# SCH_LatencyMeter_Loc2_2024-01-18.net
KiCad netlist of a schematic drawn in EasyEDA
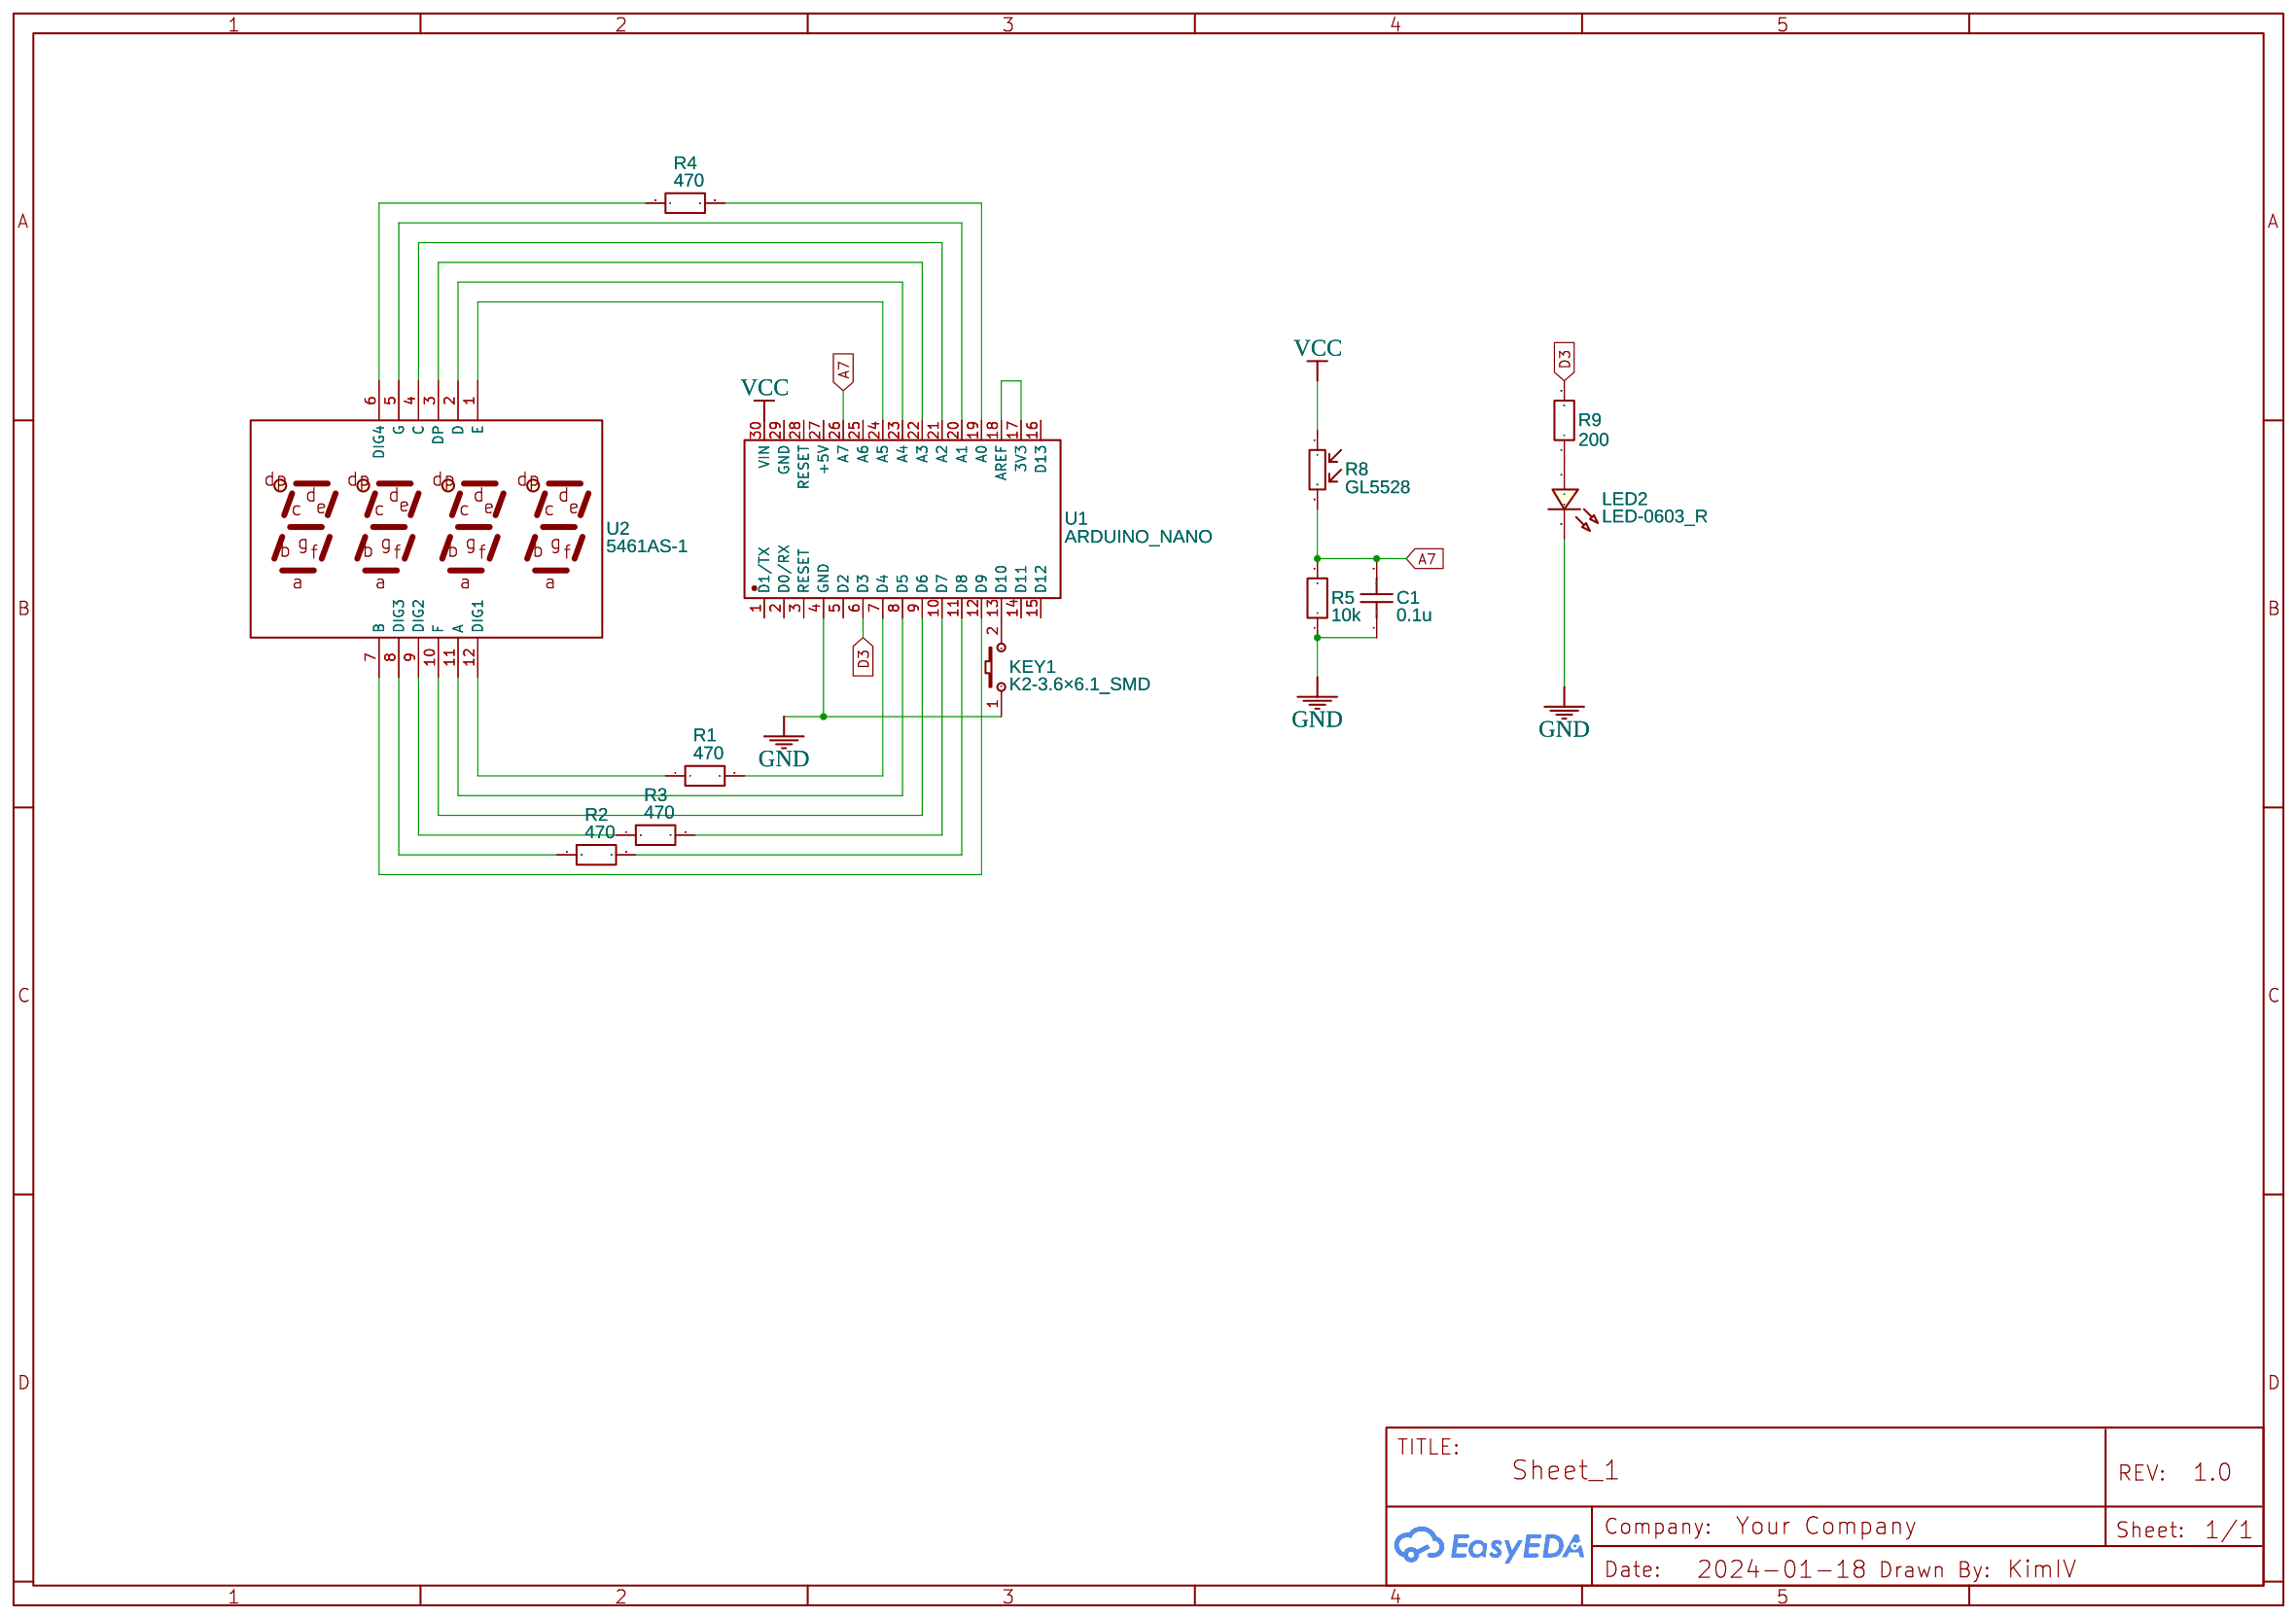
[diagram p0: schematic sheet]

(export (version "E")
  (design (tool "Eeschema 10.0.6"))
  (components
    (comp (ref "C1") (value "0.1u") (libsource (lib "") (part "C_0603_US")))
    (comp (ref "KEY1")
      (value "K2-3.6×6.1_SMD")
      (fields (field (name "Manufacturer Part") "K2-1107ST-A4SW-06"))
      (libsource (lib "") (part "K2-3.6×6.1_SMD"))
    )
    (comp (ref "LED2")
      (value "LED-0603_R")
      (fields
        (field (name "Manufacturer Part") "19-217/R6C-AL1M2VY/3T")
        (field (name "Manufacturer") "EVERLIGHT(台湾亿光)")
      )
      (libsource (lib "") (part "LED-0603_R"))
    )
    (comp (ref "R1") (value "470") (libsource (lib "") (part "R_0603_EU_1")))
    (comp (ref "R2") (value "470") (libsource (lib "") (part "R_0603_EU_1")))
    (comp (ref "R3") (value "470") (libsource (lib "") (part "R_0603_EU_1")))
    (comp (ref "R4") (value "470") (libsource (lib "") (part "R_0603_EU_1")))
    (comp (ref "R5") (value "10k") (libsource (lib "") (part "R_0603_EU")))
    (comp (ref "R8")
      (value "GL5528")
      (fields (field (name "Manufacturer") "森霸"))
      (libsource (lib "") (part "GL5528"))
    )
    (comp (ref "R9") (value "200") (libsource (lib "") (part "R_0603_EU")))
    (comp (ref "U1") (value "ARDUINO_NANO") (libsource (lib "") (part "ARDUINO_NANO")))
    (comp (ref "U2") (value "5461AS-1") (libsource (lib "") (part "5461AS-1")))
  )
  (nets
    (net (code "1") (name "A7") (class "Default")
      (node (ref "C1") (pin "2") (pinfunction "2_2") (pintype "unspecified"))
      (node (ref "R5") (pin "2") (pinfunction "2_2") (pintype "unspecified"))
      (node (ref "R8") (pin "2") (pinfunction "2_2") (pintype "input"))
      (node (ref "U1") (pin "26") (pinfunction "A7_26") (pintype "unspecified"))
    )
    (net (code "2") (name "D3") (class "Default")
      (node (ref "R9") (pin "2") (pinfunction "2_2") (pintype "unspecified"))
      (node (ref "U1") (pin "6") (pinfunction "D3_6") (pintype "unspecified"))
    )
    (net (code "3") (name "GND") (class "Default")
      (node (ref "C1") (pin "1") (pinfunction "1_1") (pintype "unspecified"))
      (node (ref "KEY1") (pin "1") (pinfunction "1_1") (pintype "unspecified"))
      (node (ref "LED2") (pin "2") (pinfunction "2_2") (pintype "unspecified"))
      (node (ref "R5") (pin "1") (pinfunction "1_1") (pintype "unspecified"))
      (node (ref "U1") (pin "4") (pinfunction "GND_4") (pintype "unspecified"))
    )
    (net (code "4") (name "Net-(LED2-Pad1)") (class "Default")
      (node (ref "LED2") (pin "1") (pinfunction "1_1") (pintype "unspecified"))
      (node (ref "R9") (pin "1") (pinfunction "1_1") (pintype "unspecified"))
    )
    (net (code "5") (name "Net-(U1-3V3)") (class "Default")
      (node (ref "U1") (pin "17") (pinfunction "3V3_17") (pintype "unspecified"))
      (node (ref "U1") (pin "18") (pinfunction "AREF_18") (pintype "unspecified"))
    )
    (net (code "6") (name "Net-(U1-A0)") (class "Default")
      (node (ref "R4") (pin "2") (pinfunction "2_2") (pintype "unspecified"))
      (node (ref "U1") (pin "19") (pinfunction "A0_19") (pintype "unspecified"))
    )
    (net (code "7") (name "Net-(U1-A1)") (class "Default")
      (node (ref "U1") (pin "20") (pinfunction "A1_20") (pintype "unspecified"))
      (node (ref "U2") (pin "5") (pinfunction "G_5") (pintype "input"))
    )
    (net (code "8") (name "Net-(U1-A2)") (class "Default")
      (node (ref "U1") (pin "21") (pinfunction "A2_21") (pintype "unspecified"))
      (node (ref "U2") (pin "4") (pinfunction "C_4") (pintype "input"))
    )
    (net (code "9") (name "Net-(U1-A3)") (class "Default")
      (node (ref "U1") (pin "22") (pinfunction "A3_22") (pintype "unspecified"))
      (node (ref "U2") (pin "3") (pinfunction "DP_3") (pintype "input"))
    )
    (net (code "10") (name "Net-(U1-A4)") (class "Default")
      (node (ref "U1") (pin "23") (pinfunction "A4_23") (pintype "unspecified"))
      (node (ref "U2") (pin "2") (pinfunction "D_2") (pintype "input"))
    )
    (net (code "11") (name "Net-(U1-A5)") (class "Default")
      (node (ref "U1") (pin "24") (pinfunction "A5_24") (pintype "unspecified"))
      (node (ref "U2") (pin "1") (pinfunction "E_1") (pintype "input"))
    )
    (net (code "12") (name "Net-(U1-D4)") (class "Default")
      (node (ref "R1") (pin "2") (pinfunction "2_2") (pintype "unspecified"))
      (node (ref "U1") (pin "7") (pinfunction "D4_7") (pintype "unspecified"))
    )
    (net (code "13") (name "Net-(U1-D5)") (class "Default")
      (node (ref "U1") (pin "8") (pinfunction "D5_8") (pintype "unspecified"))
      (node (ref "U2") (pin "11") (pinfunction "A_11") (pintype "input"))
    )
    (net (code "14") (name "Net-(U1-D6)") (class "Default")
      (node (ref "U1") (pin "9") (pinfunction "D6_9") (pintype "unspecified"))
      (node (ref "U2") (pin "10") (pinfunction "F_10") (pintype "input"))
    )
    (net (code "15") (name "Net-(U1-D7)") (class "Default")
      (node (ref "R3") (pin "2") (pinfunction "2_2") (pintype "unspecified"))
      (node (ref "U1") (pin "10") (pinfunction "D7_10") (pintype "unspecified"))
    )
    (net (code "16") (name "Net-(U1-D8)") (class "Default")
      (node (ref "R2") (pin "2") (pinfunction "2_2") (pintype "unspecified"))
      (node (ref "U1") (pin "11") (pinfunction "D8_11") (pintype "unspecified"))
    )
    (net (code "17") (name "Net-(U1-D9)") (class "Default")
      (node (ref "U1") (pin "12") (pinfunction "D9_12") (pintype "unspecified"))
      (node (ref "U2") (pin "7") (pinfunction "B_7") (pintype "input"))
    )
    (net (code "18") (name "Net-(U1-D10)") (class "Default")
      (node (ref "KEY1") (pin "2") (pinfunction "2_2") (pintype "unspecified"))
      (node (ref "U1") (pin "13") (pinfunction "D10_13") (pintype "unspecified"))
    )
    (net (code "19") (name "Net-(U2-DIG1)") (class "Default")
      (node (ref "R1") (pin "1") (pinfunction "1_1") (pintype "unspecified"))
      (node (ref "U2") (pin "12") (pinfunction "DIG1_12") (pintype "input"))
    )
    (net (code "20") (name "Net-(U2-DIG2)") (class "Default")
      (node (ref "R3") (pin "1") (pinfunction "1_1") (pintype "unspecified"))
      (node (ref "U2") (pin "9") (pinfunction "DIG2_9") (pintype "input"))
    )
    (net (code "21") (name "Net-(U2-DIG3)") (class "Default")
      (node (ref "R2") (pin "1") (pinfunction "1_1") (pintype "unspecified"))
      (node (ref "U2") (pin "8") (pinfunction "DIG3_8") (pintype "input"))
    )
    (net (code "22") (name "Net-(U2-DIG4)") (class "Default")
      (node (ref "R4") (pin "1") (pinfunction "1_1") (pintype "unspecified"))
      (node (ref "U2") (pin "6") (pinfunction "DIG4_6") (pintype "input"))
    )
    (net (code "23") (name "VCC") (class "Default")
      (node (ref "R8") (pin "1") (pinfunction "1_1") (pintype "input"))
      (node (ref "U1") (pin "30") (pinfunction "VIN_30") (pintype "unspecified"))
    )
    (net (code "24") (name "unconnected-(U1-+5V-Pad27)") (class "Default")
      (node (ref "U1") (pin "27") (pinfunction "+5V_27") (pintype "unspecified"))
    )
    (net (code "25") (name "unconnected-(U1-A6-Pad25)") (class "Default")
      (node (ref "U1") (pin "25") (pinfunction "A6_25") (pintype "unspecified"))
    )
    (net (code "26") (name "unconnected-(U1-D0{slash}RX-Pad2)") (class "Default")
      (node (ref "U1") (pin "2") (pinfunction "D0/RX_2") (pintype "unspecified"))
    )
    (net (code "27") (name "unconnected-(U1-D1{slash}TX-Pad1)") (class "Default")
      (node (ref "U1") (pin "1") (pinfunction "D1/TX_1") (pintype "unspecified"))
    )
    (net (code "28") (name "unconnected-(U1-D2-Pad5)") (class "Default")
      (node (ref "U1") (pin "5") (pinfunction "D2_5") (pintype "unspecified"))
    )
    (net (code "29") (name "unconnected-(U1-D11-Pad14)") (class "Default")
      (node (ref "U1") (pin "14") (pinfunction "D11_14") (pintype "unspecified"))
    )
    (net (code "30") (name "unconnected-(U1-D12-Pad15)") (class "Default")
      (node (ref "U1") (pin "15") (pinfunction "D12_15") (pintype "unspecified"))
    )
    (net (code "31") (name "unconnected-(U1-D13-Pad16)") (class "Default")
      (node (ref "U1") (pin "16") (pinfunction "D13_16") (pintype "unspecified"))
    )
    (net (code "32") (name "unconnected-(U1-GND-Pad29)") (class "Default")
      (node (ref "U1") (pin "29") (pinfunction "GND_29") (pintype "unspecified"))
    )
    (net (code "33") (name "unconnected-(U1-RESET-Pad3)") (class "Default")
      (node (ref "U1") (pin "3") (pinfunction "RESET_3") (pintype "unspecified"))
    )
    (net (code "34") (name "unconnected-(U1-RESET-Pad28)") (class "Default")
      (node (ref "U1") (pin "28") (pinfunction "RESET_28") (pintype "unspecified"))
    )
  )
)
